# Hub.net
KiCad netlist of a schematic drawn in EAGLE
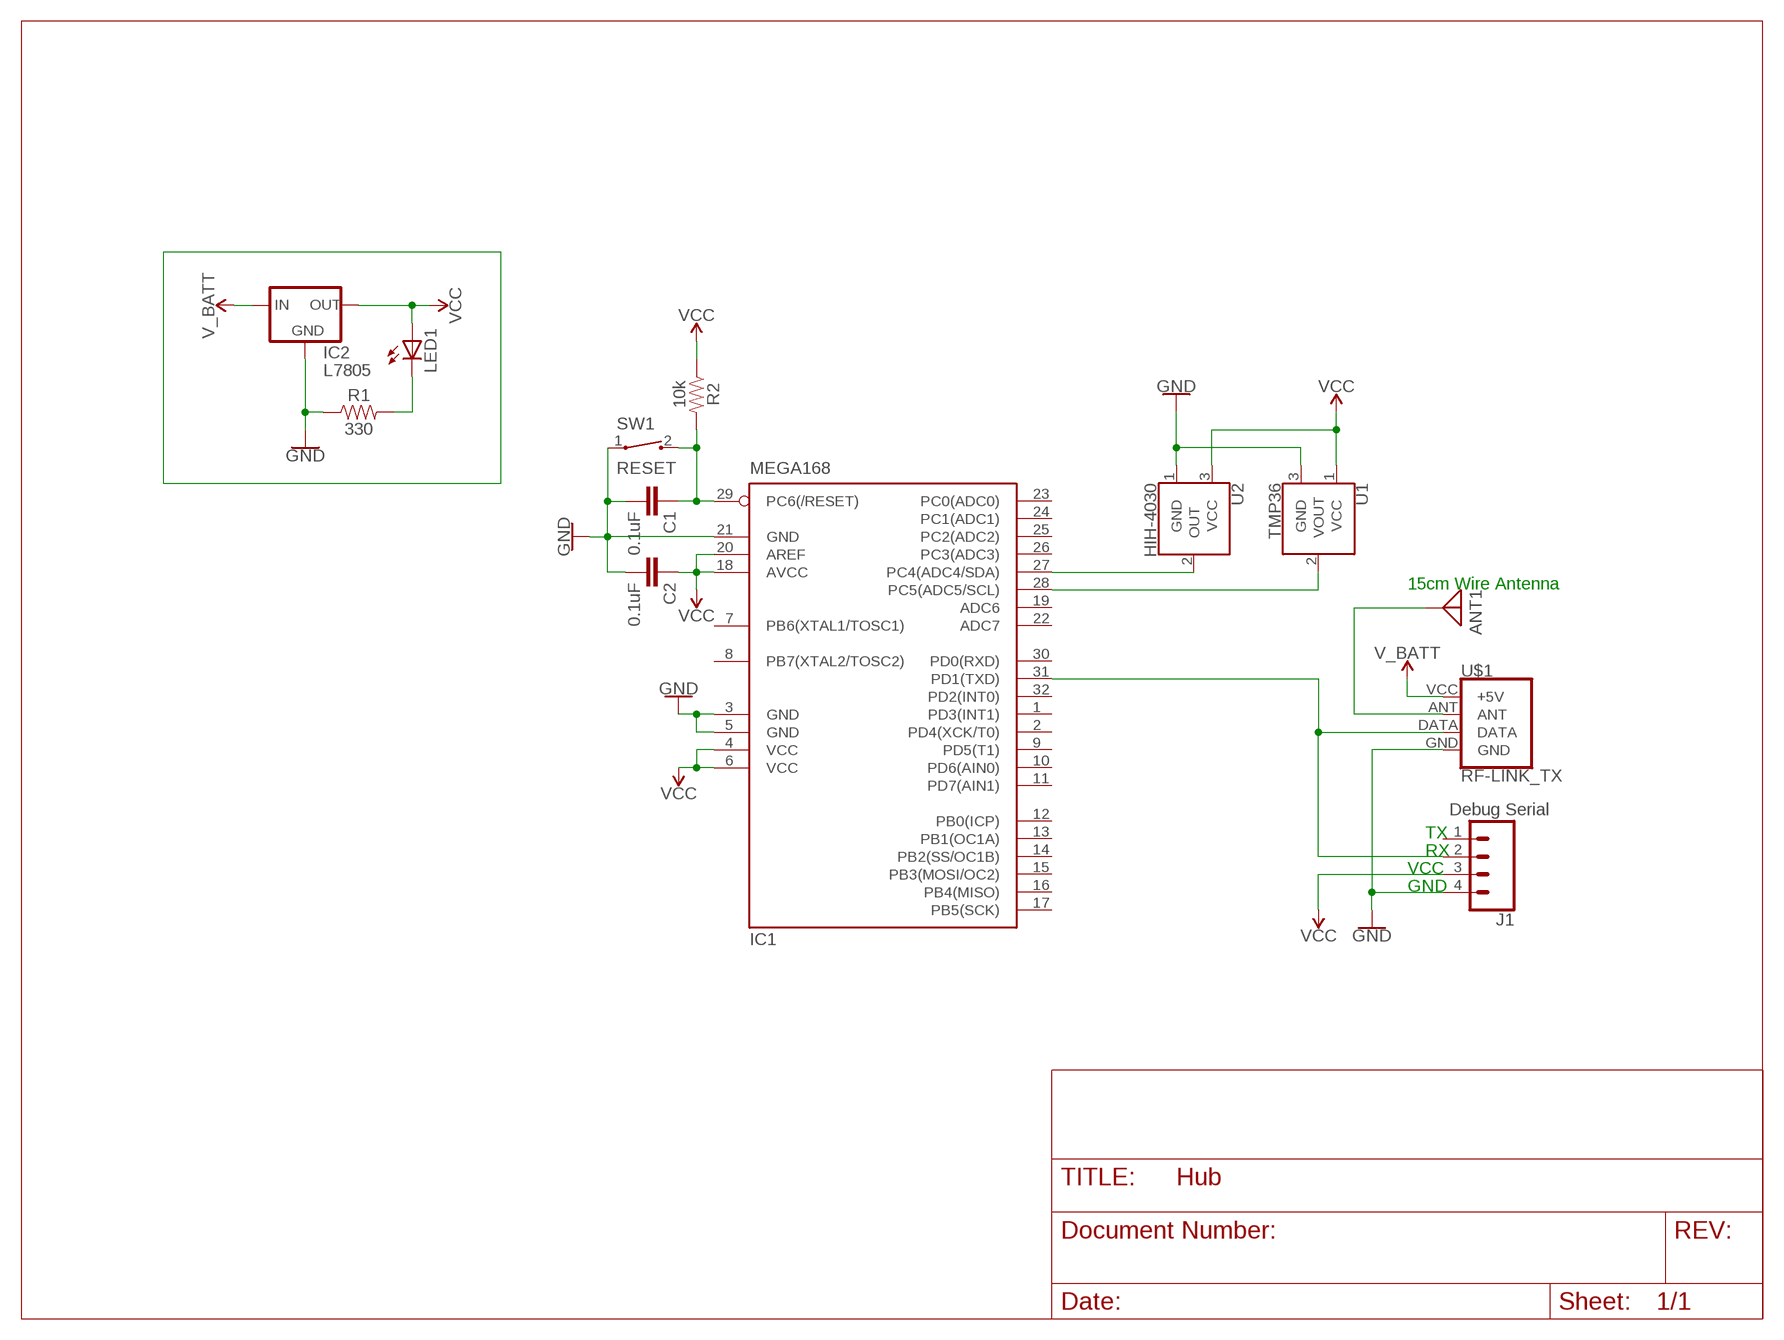
[diagram p0: schematic, sheet 1]

(export (version "E")
  (design (tool "Eeschema 10.0.6"))
  (components
    (comp (ref "ANT1")
      (value "ANTENNA")
      (footprint "eagle-import:PAD-01")
      (libsource (lib "eagle-import") (part "ANTENNA"))
    )
    (comp (ref "C1")
      (value "0.1uF")
      (footprint "eagle-import:0402")
      (libsource (lib "eagle-import") (part "0.1UF-0402-16V-10%"))
    )
    (comp (ref "C2")
      (value "0.1uF")
      (footprint "eagle-import:0402")
      (libsource (lib "eagle-import") (part "0.1UF-0402-16V-10%"))
    )
    (comp (ref "IC1")
      (value "MEGA168")
      (footprint "eagle-import:TQFP32-08")
      (fields (field (name "MPN") "ATMEGA8-16AU"))
      (libsource (lib "eagle-import") (part "MEGA8-AI"))
    )
    (comp (ref "IC2")
      (value "L7805")
      (footprint "eagle-import:78LXX")
      (libsource (lib "eagle-import") (part "78LXX"))
    )
    (comp (ref "J1")
      (value "CONN_04")
      (footprint "eagle-import:1X04")
      (fields (field (name "PROD_ID") "CONN-09696") (field (name "PROD_ID_1") "Debug Serial"))
      (libsource (lib "eagle-import") (part "CONN_04"))
    )
    (comp (ref "LED1")
      (value "LED")
      (footprint "eagle-import:SMARTLED-TTW")
      (libsource (lib "eagle-import") (part "LED"))
    )
    (comp (ref "R1")
      (value "330")
      (footprint "eagle-import:0603")
      (libsource (lib "eagle-import") (part "330OHM-0603-1/10W-1%"))
    )
    (comp (ref "R2")
      (value "10k")
      (footprint "eagle-import:0603")
      (libsource (lib "eagle-import") (part "10KOHM-0603-1/10W-1%"))
    )
    (comp (ref "SW1")
      (value "RESET")
      (footprint "eagle-import:CT10-XXXX-A2")
      (libsource (lib "eagle-import") (part "CT10-XXXX-A2"))
    )
    (comp (ref "U$1")
      (value "RF-LINK_TX")
      (footprint "eagle-import:RF-LINK_TX")
      (libsource (lib "eagle-import") (part "RF-LINK_TX"))
    )
    (comp (ref "U1")
      (value "TMP36")
      (footprint "eagle-import:TO-92")
      (libsource (lib "eagle-import") (part "TMP36GT9"))
    )
    (comp (ref "U2")
      (value "HIH-4030")
      (footprint "eagle-import:HIH-4030")
      (libsource (lib "eagle-import") (part "HIH-4030"))
    )
  )
  (nets
    (net (code "1") (name "GND") (class "Default")
      (node (ref "C1") (pin "2") (pinfunction "2_2") (pintype "passive"))
      (node (ref "C2") (pin "2") (pinfunction "2_2") (pintype "passive"))
      (node (ref "IC1") (pin "21") (pinfunction "GND_21") (pintype "power_in"))
      (node (ref "IC1") (pin "3") (pinfunction "GND_3") (pintype "power_in"))
      (node (ref "IC1") (pin "5") (pinfunction "GND_5") (pintype "power_in"))
      (node (ref "IC2") (pin "GND") (pinfunction "GND_GND") (pintype "input"))
      (node (ref "J1") (pin "4") (pinfunction "4_4") (pintype "passive"))
      (node (ref "R1") (pin "1") (pinfunction "1_1") (pintype "passive"))
      (node (ref "SW1") (pin "1") (pinfunction "1_1") (pintype "passive"))
      (node (ref "U$1") (pin "GND") (pinfunction "GND_GND") (pintype "power_in"))
      (node (ref "U1") (pin "3") (pinfunction "GND_3") (pintype "bidirectional"))
      (node (ref "U2") (pin "1") (pinfunction "GND_1") (pintype "bidirectional"))
    )
    (net (code "2") (name "Net-(ANT1-Pad1)") (class "Default")
      (node (ref "ANT1") (pin "1") (pinfunction "1_1") (pintype "output"))
      (node (ref "U$1") (pin "ANT") (pinfunction "ANT_ANT") (pintype "passive"))
    )
    (net (code "3") (name "Net-(IC1-PC4(ADC4{slash}SDA))") (class "Default")
      (node (ref "IC1") (pin "27") (pinfunction "PC4(ADC4/SDA)_27") (pintype "bidirectional"))
      (node (ref "U2") (pin "2") (pinfunction "OUT_2") (pintype "bidirectional"))
    )
    (net (code "4") (name "Net-(IC1-PC5(ADC5{slash}SCL))") (class "Default")
      (node (ref "IC1") (pin "28") (pinfunction "PC5(ADC5/SCL)_28") (pintype "bidirectional"))
      (node (ref "U1") (pin "2") (pinfunction "VOUT_2") (pintype "bidirectional"))
    )
    (net (code "5") (name "Net-(IC1-PC6({slash}RESET))") (class "Default")
      (node (ref "C1") (pin "1") (pinfunction "1_1") (pintype "passive"))
      (node (ref "IC1") (pin "29") (pinfunction "PC6(/RESET)_29") (pintype "bidirectional"))
      (node (ref "R2") (pin "2") (pinfunction "2_2") (pintype "passive"))
      (node (ref "SW1") (pin "2") (pinfunction "2_2") (pintype "passive"))
    )
    (net (code "6") (name "Net-(IC1-PD1(TXD))") (class "Default")
      (node (ref "IC1") (pin "31") (pinfunction "PD1(TXD)_31") (pintype "bidirectional"))
      (node (ref "J1") (pin "2") (pinfunction "2_2") (pintype "passive"))
      (node (ref "U$1") (pin "DATA") (pinfunction "DATA_DATA") (pintype "input"))
    )
    (net (code "7") (name "Net-(LED1-C)") (class "Default")
      (node (ref "LED1") (pin "C@1") (pinfunction "C_C@1") (pintype "passive"))
      (node (ref "R1") (pin "2") (pinfunction "2_2") (pintype "passive"))
    )
    (net (code "8") (name "VCC") (class "Default")
      (node (ref "C2") (pin "1") (pinfunction "1_1") (pintype "passive"))
      (node (ref "IC1") (pin "18") (pinfunction "AVCC_18") (pintype "power_in"))
      (node (ref "IC1") (pin "20") (pinfunction "AREF_20") (pintype "passive"))
      (node (ref "IC1") (pin "4") (pinfunction "VCC_4") (pintype "power_in"))
      (node (ref "IC1") (pin "6") (pinfunction "VCC_6") (pintype "power_in"))
      (node (ref "IC2") (pin "OUT") (pinfunction "OUT_OUT") (pintype "passive"))
      (node (ref "J1") (pin "3") (pinfunction "3_3") (pintype "passive"))
      (node (ref "LED1") (pin "A@1") (pinfunction "A_A@1") (pintype "passive"))
      (node (ref "R2") (pin "1") (pinfunction "1_1") (pintype "passive"))
      (node (ref "U1") (pin "1") (pinfunction "VCC_1") (pintype "bidirectional"))
      (node (ref "U2") (pin "3") (pinfunction "VCC_3") (pintype "bidirectional"))
    )
    (net (code "9") (name "V_BATT") (class "Default")
      (node (ref "IC2") (pin "IN") (pinfunction "IN_IN") (pintype "input"))
      (node (ref "U$1") (pin "VCC") (pinfunction "+5V_VCC") (pintype "power_in"))
    )
    (net (code "10") (name "unconnected-(IC1-ADC6-Pad19)") (class "Default")
      (node (ref "IC1") (pin "19") (pinfunction "ADC6_19") (pintype "bidirectional"))
    )
    (net (code "11") (name "unconnected-(IC1-ADC7-Pad22)") (class "Default")
      (node (ref "IC1") (pin "22") (pinfunction "ADC7_22") (pintype "bidirectional"))
    )
    (net (code "12") (name "unconnected-(IC1-PB0(ICP)-Pad12)") (class "Default")
      (node (ref "IC1") (pin "12") (pinfunction "PB0(ICP)_12") (pintype "bidirectional"))
    )
    (net (code "13") (name "unconnected-(IC1-PB1(OC1A)-Pad13)") (class "Default")
      (node (ref "IC1") (pin "13") (pinfunction "PB1(OC1A)_13") (pintype "bidirectional"))
    )
    (net (code "14") (name "unconnected-(IC1-PB2(SS{slash}OC1B)-Pad14)") (class "Default")
      (node (ref "IC1") (pin "14") (pinfunction "PB2(SS/OC1B)_14") (pintype "bidirectional"))
    )
    (net (code "15") (name "unconnected-(IC1-PB3(MOSI{slash}OC2)-Pad15)") (class "Default")
      (node (ref "IC1") (pin "15") (pinfunction "PB3(MOSI/OC2)_15") (pintype "bidirectional"))
    )
    (net (code "16") (name "unconnected-(IC1-PB4(MISO)-Pad16)") (class "Default")
      (node (ref "IC1") (pin "16") (pinfunction "PB4(MISO)_16") (pintype "bidirectional"))
    )
    (net (code "17") (name "unconnected-(IC1-PB5(SCK)-Pad17)") (class "Default")
      (node (ref "IC1") (pin "17") (pinfunction "PB5(SCK)_17") (pintype "bidirectional"))
    )
    (net (code "18") (name "unconnected-(IC1-PB6(XTAL1{slash}TOSC1)-Pad7)") (class "Default")
      (node (ref "IC1") (pin "7") (pinfunction "PB6(XTAL1/TOSC1)_7") (pintype "bidirectional"))
    )
    (net (code "19") (name "unconnected-(IC1-PB7(XTAL2{slash}TOSC2)-Pad8)") (class "Default")
      (node (ref "IC1") (pin "8") (pinfunction "PB7(XTAL2/TOSC2)_8") (pintype "bidirectional"))
    )
    (net (code "20") (name "unconnected-(IC1-PC0(ADC0)-Pad23)") (class "Default")
      (node (ref "IC1") (pin "23") (pinfunction "PC0(ADC0)_23") (pintype "bidirectional"))
    )
    (net (code "21") (name "unconnected-(IC1-PC1(ADC1)-Pad24)") (class "Default")
      (node (ref "IC1") (pin "24") (pinfunction "PC1(ADC1)_24") (pintype "bidirectional"))
    )
    (net (code "22") (name "unconnected-(IC1-PC2(ADC2)-Pad25)") (class "Default")
      (node (ref "IC1") (pin "25") (pinfunction "PC2(ADC2)_25") (pintype "bidirectional"))
    )
    (net (code "23") (name "unconnected-(IC1-PC3(ADC3)-Pad26)") (class "Default")
      (node (ref "IC1") (pin "26") (pinfunction "PC3(ADC3)_26") (pintype "bidirectional"))
    )
    (net (code "24") (name "unconnected-(IC1-PD0(RXD)-Pad30)") (class "Default")
      (node (ref "IC1") (pin "30") (pinfunction "PD0(RXD)_30") (pintype "bidirectional"))
    )
    (net (code "25") (name "unconnected-(IC1-PD2(INT0)-Pad32)") (class "Default")
      (node (ref "IC1") (pin "32") (pinfunction "PD2(INT0)_32") (pintype "bidirectional"))
    )
    (net (code "26") (name "unconnected-(IC1-PD3(INT1)-Pad1)") (class "Default")
      (node (ref "IC1") (pin "1") (pinfunction "PD3(INT1)_1") (pintype "bidirectional"))
    )
    (net (code "27") (name "unconnected-(IC1-PD4(XCK{slash}T0)-Pad2)") (class "Default")
      (node (ref "IC1") (pin "2") (pinfunction "PD4(XCK/T0)_2") (pintype "bidirectional"))
    )
    (net (code "28") (name "unconnected-(IC1-PD5(T1)-Pad9)") (class "Default")
      (node (ref "IC1") (pin "9") (pinfunction "PD5(T1)_9") (pintype "bidirectional"))
    )
    (net (code "29") (name "unconnected-(IC1-PD6(AIN0)-Pad10)") (class "Default")
      (node (ref "IC1") (pin "10") (pinfunction "PD6(AIN0)_10") (pintype "bidirectional"))
    )
    (net (code "30") (name "unconnected-(IC1-PD7(AIN1)-Pad11)") (class "Default")
      (node (ref "IC1") (pin "11") (pinfunction "PD7(AIN1)_11") (pintype "bidirectional"))
    )
    (net (code "31") (name "unconnected-(J1-Pad1)") (class "Default")
      (node (ref "J1") (pin "1") (pinfunction "1_1") (pintype "passive"))
    )
  )
)
